# Fastino_References.net
KiCad netlist of a schematic drawn in Altium Designer
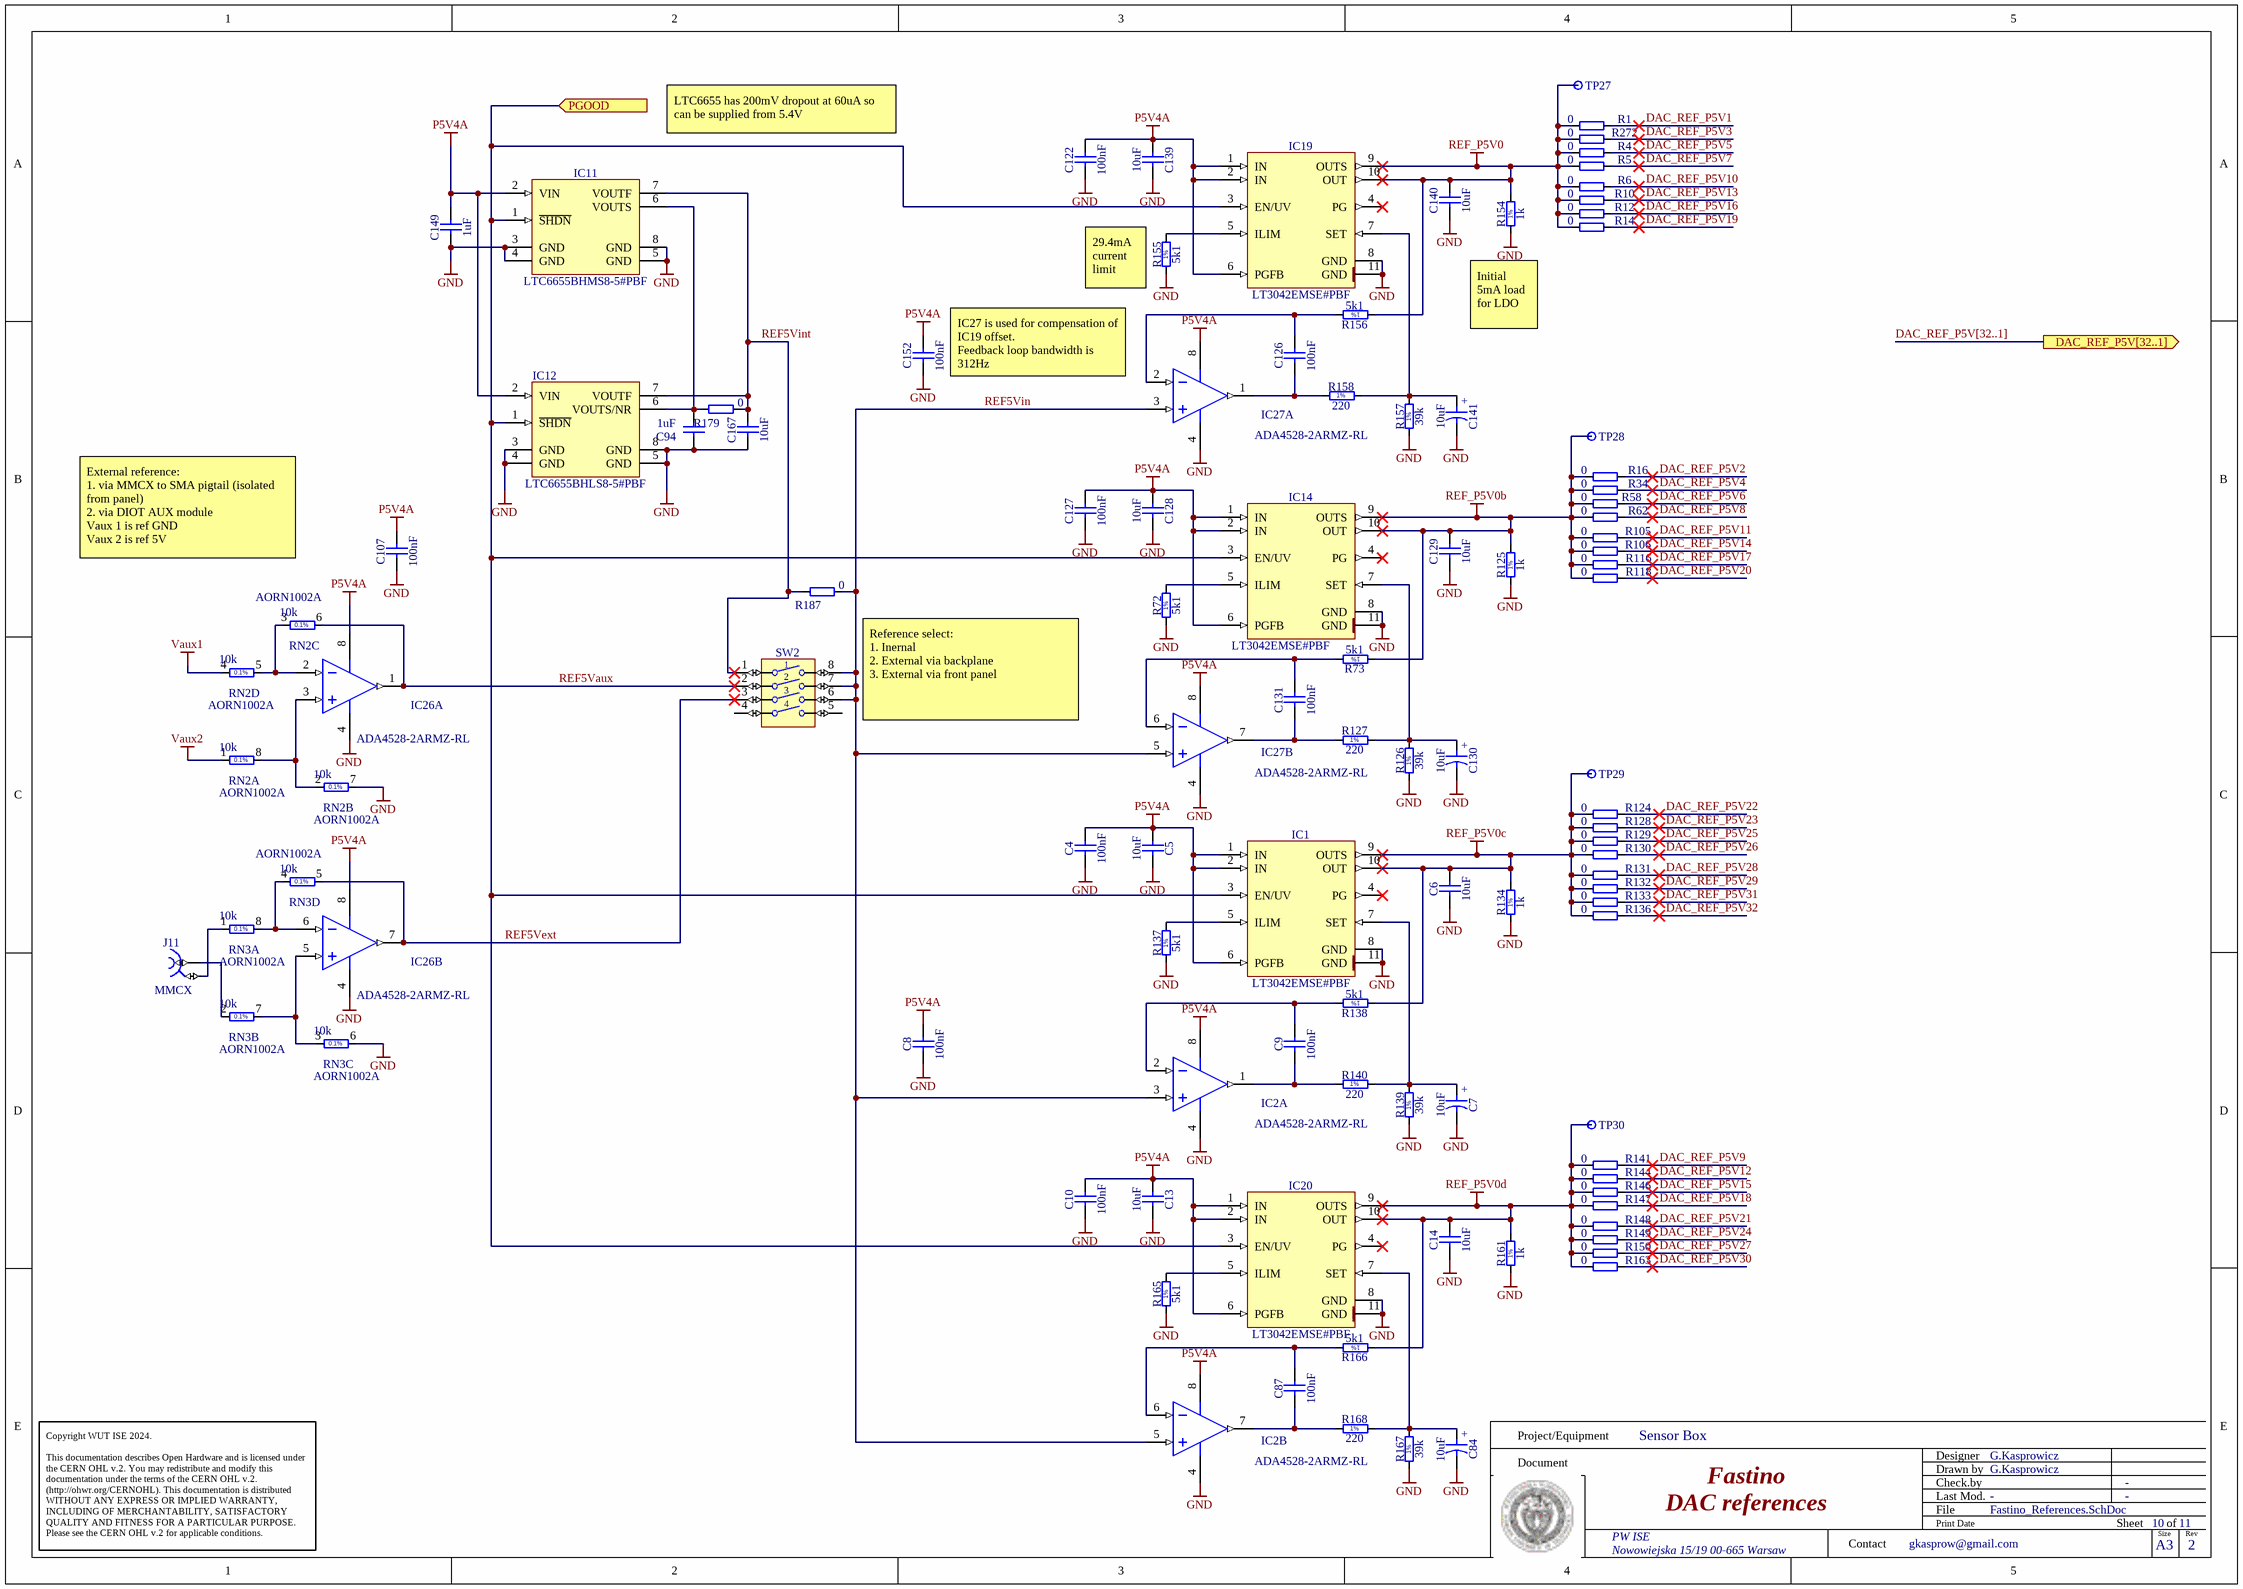
[diagram p0: Fastino_References.SchDoc]

(export (version "E")
  (design (tool "Eeschema 10.0.6"))
  (components
    (comp (ref "C4")
      (value "100nF")
      (footprint "CAPC1005X55N")
      (description "Non-polarised capacitor")
      (fields (field (name "PART NUMBER") "CC0402_100NF_16V_10%_X5R") (field (name "VOLTAGE") "16V"))
      (libsource (lib "Capacitors") (part "Capacitor - non polarized"))
    )
    (comp (ref "C5")
      (value "10uF")
      (footprint "CAPC1608X80N")
      (description "Non-polarised capacitor")
      (fields (field (name "PART NUMBER") "CC0603_10UF_10V_10%_X5R") (field (name "VOLTAGE") "10V"))
      (libsource (lib "Capacitors") (part "Capacitor - non polarized"))
    )
    (comp (ref "C6")
      (value "10uF")
      (footprint "CAPC1608X80N")
      (description "Non-polarised capacitor")
      (fields (field (name "PART NUMBER") "CC0603_10UF_10V_10%_X5R") (field (name "VOLTAGE") "10V"))
      (libsource (lib "Capacitors") (part "Capacitor - non polarized"))
    )
    (comp (ref "C7")
      (value "10uF")
      (footprint "CAPMP3216X180N")
      (description "Polarised capacitor")
      (fields (field (name "PART NUMBER") "CTE3216-18_10UF_16V_20%_AVX_TCJ") (field (name "VOLTAGE") "16V"))
      (libsource (lib "Capacitors") (part "Capacitor - polarized"))
    )
    (comp (ref "C8")
      (value "100nF")
      (footprint "CAPC1005X55N")
      (description "Non-polarised capacitor")
      (fields (field (name "PART NUMBER") "CC0402_100NF_16V_10%_X5R") (field (name "VOLTAGE") "16V"))
      (libsource (lib "Capacitors") (part "Capacitor - non polarized"))
    )
    (comp (ref "C9")
      (value "100nF")
      (footprint "CAPC1005X55N")
      (description "Non-polarised capacitor")
      (fields (field (name "PART NUMBER") "CC0402_100NF_16V_10%_X5R") (field (name "VOLTAGE") "16V"))
      (libsource (lib "Capacitors") (part "Capacitor - non polarized"))
    )
    (comp (ref "C10")
      (value "100nF")
      (footprint "CAPC1005X55N")
      (description "Non-polarised capacitor")
      (fields (field (name "PART NUMBER") "CC0402_100NF_16V_10%_X5R") (field (name "VOLTAGE") "16V"))
      (libsource (lib "Capacitors") (part "Capacitor - non polarized"))
    )
    (comp (ref "C13")
      (value "10uF")
      (footprint "CAPC1608X80N")
      (description "Non-polarised capacitor")
      (fields (field (name "PART NUMBER") "CC0603_10UF_10V_10%_X5R") (field (name "VOLTAGE") "10V"))
      (libsource (lib "Capacitors") (part "Capacitor - non polarized"))
    )
    (comp (ref "C14")
      (value "10uF")
      (footprint "CAPC1608X80N")
      (description "Non-polarised capacitor")
      (fields (field (name "PART NUMBER") "CC0603_10UF_10V_10%_X5R") (field (name "VOLTAGE") "10V"))
      (libsource (lib "Capacitors") (part "Capacitor - non polarized"))
    )
    (comp (ref "C84")
      (value "10uF")
      (footprint "CAPMP3216X180N")
      (description "Polarised capacitor")
      (fields (field (name "PART NUMBER") "CTE3216-18_10UF_16V_20%_AVX_TCJ") (field (name "VOLTAGE") "16V"))
      (libsource (lib "Capacitors") (part "Capacitor - polarized"))
    )
    (comp (ref "C87")
      (value "100nF")
      (footprint "CAPC1005X55N")
      (description "Non-polarised capacitor")
      (fields (field (name "PART NUMBER") "CC0402_100NF_16V_10%_X5R") (field (name "VOLTAGE") "16V"))
      (libsource (lib "Capacitors") (part "Capacitor - non polarized"))
    )
    (comp (ref "C94")
      (value "1uF")
      (footprint "CAPC1608X87N")
      (description "Non-polarised capacitor")
      (fields (field (name "PART NUMBER") "CC0603_1UF_25V_10%_X7R") (field (name "VOLTAGE") "25V"))
      (libsource (lib "Capacitors") (part "Capacitor - non polarized"))
    )
    (comp (ref "C107")
      (value "100nF")
      (footprint "CAPC1005X55N")
      (description "Non-polarised capacitor")
      (fields (field (name "PART NUMBER") "CC0402_100NF_16V_10%_X5R") (field (name "VOLTAGE") "16V"))
      (libsource (lib "Capacitors") (part "Capacitor - non polarized"))
    )
    (comp (ref "C122")
      (value "100nF")
      (footprint "CAPC1005X55N")
      (description "Non-polarised capacitor")
      (fields (field (name "PART NUMBER") "CC0402_100NF_16V_10%_X5R") (field (name "VOLTAGE") "16V"))
      (libsource (lib "Capacitors") (part "Capacitor - non polarized"))
    )
    (comp (ref "C126")
      (value "100nF")
      (footprint "CAPC1005X55N")
      (description "Non-polarised capacitor")
      (fields (field (name "PART NUMBER") "CC0402_100NF_16V_10%_X5R") (field (name "VOLTAGE") "16V"))
      (libsource (lib "Capacitors") (part "Capacitor - non polarized"))
    )
    (comp (ref "C127")
      (value "100nF")
      (footprint "CAPC1005X55N")
      (description "Non-polarised capacitor")
      (fields (field (name "PART NUMBER") "CC0402_100NF_16V_10%_X5R") (field (name "VOLTAGE") "16V"))
      (libsource (lib "Capacitors") (part "Capacitor - non polarized"))
    )
    (comp (ref "C128")
      (value "10uF")
      (footprint "CAPC1608X80N")
      (description "Non-polarised capacitor")
      (fields (field (name "PART NUMBER") "CC0603_10UF_10V_10%_X5R") (field (name "VOLTAGE") "10V"))
      (libsource (lib "Capacitors") (part "Capacitor - non polarized"))
    )
    (comp (ref "C129")
      (value "10uF")
      (footprint "CAPC1608X80N")
      (description "Non-polarised capacitor")
      (fields (field (name "PART NUMBER") "CC0603_10UF_10V_10%_X5R") (field (name "VOLTAGE") "10V"))
      (libsource (lib "Capacitors") (part "Capacitor - non polarized"))
    )
    (comp (ref "C130")
      (value "10uF")
      (footprint "CAPMP3216X180N")
      (description "Polarised capacitor")
      (fields (field (name "PART NUMBER") "CTE3216-18_10UF_16V_20%_AVX_TCJ") (field (name "VOLTAGE") "16V"))
      (libsource (lib "Capacitors") (part "Capacitor - polarized"))
    )
    (comp (ref "C131")
      (value "100nF")
      (footprint "CAPC1005X55N")
      (description "Non-polarised capacitor")
      (fields (field (name "PART NUMBER") "CC0402_100NF_16V_10%_X5R") (field (name "VOLTAGE") "16V"))
      (libsource (lib "Capacitors") (part "Capacitor - non polarized"))
    )
    (comp (ref "C139")
      (value "10uF")
      (footprint "CAPC1608X80N")
      (description "Non-polarised capacitor")
      (fields (field (name "PART NUMBER") "CC0603_10UF_10V_10%_X5R") (field (name "VOLTAGE") "10V"))
      (libsource (lib "Capacitors") (part "Capacitor - non polarized"))
    )
    (comp (ref "C140")
      (value "10uF")
      (footprint "CAPC1608X80N")
      (description "Non-polarised capacitor")
      (fields (field (name "PART NUMBER") "CC0603_10UF_10V_10%_X5R") (field (name "VOLTAGE") "10V"))
      (libsource (lib "Capacitors") (part "Capacitor - non polarized"))
    )
    (comp (ref "C141")
      (value "10uF")
      (footprint "CAPMP3216X180N")
      (description "Polarised capacitor")
      (fields (field (name "PART NUMBER") "CTE3216-18_10UF_16V_20%_AVX_TCJ") (field (name "VOLTAGE") "16V"))
      (libsource (lib "Capacitors") (part "Capacitor - polarized"))
    )
    (comp (ref "C149")
      (value "1uF")
      (footprint "CAPC1608X87N")
      (description "Non-polarised capacitor")
      (fields (field (name "PART NUMBER") "CC0603_1UF_25V_10%_X7R") (field (name "VOLTAGE") "25V"))
      (libsource (lib "Capacitors") (part "Capacitor - non polarized"))
    )
    (comp (ref "C152")
      (value "100nF")
      (footprint "CAPC1005X55N")
      (description "Non-polarised capacitor")
      (fields (field (name "PART NUMBER") "CC0402_100NF_16V_10%_X5R") (field (name "VOLTAGE") "16V"))
      (libsource (lib "Capacitors") (part "Capacitor - non polarized"))
    )
    (comp (ref "C167")
      (value "10uF")
      (footprint "CAPC1608X80N")
      (description "Non-polarised capacitor")
      (fields (field (name "PART NUMBER") "CC0603_10UF_10V_10%_X5R") (field (name "VOLTAGE") "10V"))
      (libsource (lib "Capacitors") (part "Capacitor - non polarized"))
    )
    (comp (ref "IC1")
      (value "LT3042EMSE#PBF")
      (footprint "SOP50P490X110-11N-R168X198")
      (description "20V, 200mA, Ultralow Noise, Ultrahigh PSRR RF Linear Regulator")
      (fields (field (name "MANUFACTURER") "LINEAR TECHNOLOGY"))
      (libsource (lib "ICs And Semiconductors") (part "LT3042"))
    )
    (comp (ref "IC2")
      (value "ADA4528-2ARMZ-RL")
      (footprint "ADI-RM-8_N")
      (fields (field (name "GENERIC PART NUMBER") "ADA4528-2") (field (name "MANUFACTURER") "Analog Devices"))
      (libsource (lib "Altium Content Vault") (part "ADI-ADA4000-2-X-8"))
    )
    (comp (ref "IC11")
      (value "LTC6655BHMS8-5#PBF")
      (footprint "SOP65P490X110-8N")
      (description "0.25ppm Noise, Low Drift Precision Buffered Voltage Reference")
      (fields (field (name "MANUFACTURER") "LINEAR TECHNOLOGY"))
      (libsource (lib "ICs And Semiconductors") (part "LTC6655"))
    )
    (comp (ref "IC12")
      (value "LTC6655BHLS8-5#PBF")
      (footprint "8-CLCC")
      (description "5.0V, 1uA Precision Voltage Reference")
      (fields (field (name "MANUFACTURER") "LINEAR TECHNOLOGY"))
      (libsource (lib "Sampler") (part "REF_LTC6655CHLS8-4.096"))
    )
    (comp (ref "IC14")
      (value "LT3042EMSE#PBF")
      (footprint "SOP50P490X110-11N-R168X198")
      (description "20V, 200mA, Ultralow Noise, Ultrahigh PSRR RF Linear Regulator")
      (fields (field (name "MANUFACTURER") "LINEAR TECHNOLOGY"))
      (libsource (lib "ICs And Semiconductors") (part "LT3042"))
    )
    (comp (ref "IC19")
      (value "LT3042EMSE#PBF")
      (footprint "SOP50P490X110-11N-R168X198")
      (description "20V, 200mA, Ultralow Noise, Ultrahigh PSRR RF Linear Regulator")
      (fields (field (name "MANUFACTURER") "LINEAR TECHNOLOGY"))
      (libsource (lib "ICs And Semiconductors") (part "LT3042"))
    )
    (comp (ref "IC20")
      (value "LT3042EMSE#PBF")
      (footprint "SOP50P490X110-11N-R168X198")
      (description "20V, 200mA, Ultralow Noise, Ultrahigh PSRR RF Linear Regulator")
      (fields (field (name "MANUFACTURER") "LINEAR TECHNOLOGY"))
      (libsource (lib "ICs And Semiconductors") (part "LT3042"))
    )
    (comp (ref "IC26")
      (value "ADA4528-2ARMZ-RL")
      (footprint "ADI-RM-8_N")
      (fields (field (name "GENERIC PART NUMBER") "ADA4528-2") (field (name "MANUFACTURER") "Analog Devices"))
      (libsource (lib "Altium Content Vault") (part "ADI-ADA4000-2-X-8"))
    )
    (comp (ref "IC27")
      (value "ADA4528-2ARMZ-RL")
      (footprint "ADI-RM-8_N")
      (fields (field (name "GENERIC PART NUMBER") "ADA4528-2") (field (name "MANUFACTURER") "Analog Devices"))
      (libsource (lib "Altium Content Vault") (part "ADI-ADA4000-2-X-8"))
    )
    (comp (ref "J11")
      (value "MMCX")
      (footprint "SAMTEC_MMCX-J-P-H-ST-TH1")
      (fields
        (field (name "PART NUMBER") "SAMTEC_MMCX-J-P-H-ST-TH1")
        (field (name "MANUFACTURER") "SAMTEC")
        (field (name "MANUFACTURER PART NUMBER") "MMCX-J-P-H-ST-TH1")
      )
      (libsource (lib "Connectors") (part "Coax_1Female_1Shield"))
    )
    (comp (ref "R1")
      (value "0")
      (footprint "RESC1005X40N")
      (description "Resistor")
      (fields (field (name "PART NUMBER") "R0402_0R_JUMPER") (field (name "MANUFACTURER") "GENERIC"))
      (libsource (lib "Resistors") (part "Resistor"))
    )
    (comp (ref "R4")
      (value "0")
      (footprint "RESC1005X40N")
      (description "Resistor")
      (fields (field (name "PART NUMBER") "R0402_0R_JUMPER") (field (name "MANUFACTURER") "GENERIC"))
      (libsource (lib "Resistors") (part "Resistor"))
    )
    (comp (ref "R5")
      (value "0")
      (footprint "RESC1005X40N")
      (description "Resistor")
      (fields (field (name "PART NUMBER") "R0402_0R_JUMPER") (field (name "MANUFACTURER") "GENERIC"))
      (libsource (lib "Resistors") (part "Resistor"))
    )
    (comp (ref "R6")
      (value "0")
      (footprint "RESC1005X40N")
      (description "Resistor")
      (fields (field (name "PART NUMBER") "R0402_0R_JUMPER") (field (name "MANUFACTURER") "GENERIC"))
      (libsource (lib "Resistors") (part "Resistor"))
    )
    (comp (ref "R10")
      (value "0")
      (footprint "RESC1005X40N")
      (description "Resistor")
      (fields (field (name "PART NUMBER") "R0402_0R_JUMPER") (field (name "MANUFACTURER") "GENERIC"))
      (libsource (lib "Resistors") (part "Resistor"))
    )
    (comp (ref "R12")
      (value "0")
      (footprint "RESC1005X40N")
      (description "Resistor")
      (fields (field (name "PART NUMBER") "R0402_0R_JUMPER") (field (name "MANUFACTURER") "GENERIC"))
      (libsource (lib "Resistors") (part "Resistor"))
    )
    (comp (ref "R14")
      (value "0")
      (footprint "RESC1005X40N")
      (description "Resistor")
      (fields (field (name "PART NUMBER") "R0402_0R_JUMPER") (field (name "MANUFACTURER") "GENERIC"))
      (libsource (lib "Resistors") (part "Resistor"))
    )
    (comp (ref "R16")
      (value "0")
      (footprint "RESC1005X40N")
      (description "Resistor")
      (fields (field (name "PART NUMBER") "R0402_0R_JUMPER") (field (name "MANUFACTURER") "GENERIC"))
      (libsource (lib "Resistors") (part "Resistor"))
    )
    (comp (ref "R34")
      (value "0")
      (footprint "RESC1005X40N")
      (description "Resistor")
      (fields (field (name "PART NUMBER") "R0402_0R_JUMPER") (field (name "MANUFACTURER") "GENERIC"))
      (libsource (lib "Resistors") (part "Resistor"))
    )
    (comp (ref "R58")
      (value "0")
      (footprint "RESC1005X40N")
      (description "Resistor")
      (fields (field (name "PART NUMBER") "R0402_0R_JUMPER") (field (name "MANUFACTURER") "GENERIC"))
      (libsource (lib "Resistors") (part "Resistor"))
    )
    (comp (ref "R62")
      (value "0")
      (footprint "RESC1005X40N")
      (description "Resistor")
      (fields (field (name "PART NUMBER") "R0402_0R_JUMPER") (field (name "MANUFACTURER") "GENERIC"))
      (libsource (lib "Resistors") (part "Resistor"))
    )
    (comp (ref "R72")
      (value "5k1")
      (footprint "RESC1005X40N")
      (description "Resistor - 1%")
      (fields (field (name "PART NUMBER") "R0402_5K1_1%_0.0625W_100PPM") (field (name "POWER") "0.0625W"))
      (libsource (lib "Resistors") (part "Resistor - 1%"))
    )
    (comp (ref "R73")
      (value "5k1")
      (footprint "RESC1005X40N")
      (description "Resistor - 1%")
      (fields (field (name "PART NUMBER") "R0402_5K1_1%_0.0625W_100PPM") (field (name "POWER") "0.0625W"))
      (libsource (lib "Resistors") (part "Resistor - 1%"))
    )
    (comp (ref "R105")
      (value "0")
      (footprint "RESC1005X40N")
      (description "Resistor")
      (fields (field (name "PART NUMBER") "R0402_0R_JUMPER") (field (name "MANUFACTURER") "GENERIC"))
      (libsource (lib "Resistors") (part "Resistor"))
    )
    (comp (ref "R106")
      (value "0")
      (footprint "RESC1005X40N")
      (description "Resistor")
      (fields (field (name "PART NUMBER") "R0402_0R_JUMPER") (field (name "MANUFACTURER") "GENERIC"))
      (libsource (lib "Resistors") (part "Resistor"))
    )
    (comp (ref "R116")
      (value "0")
      (footprint "RESC1005X40N")
      (description "Resistor")
      (fields (field (name "PART NUMBER") "R0402_0R_JUMPER") (field (name "MANUFACTURER") "GENERIC"))
      (libsource (lib "Resistors") (part "Resistor"))
    )
    (comp (ref "R118")
      (value "0")
      (footprint "RESC1005X40N")
      (description "Resistor")
      (fields (field (name "PART NUMBER") "R0402_0R_JUMPER") (field (name "MANUFACTURER") "GENERIC"))
      (libsource (lib "Resistors") (part "Resistor"))
    )
    (comp (ref "R124")
      (value "0")
      (footprint "RESC1005X40N")
      (description "Resistor")
      (fields (field (name "PART NUMBER") "R0402_0R_JUMPER") (field (name "MANUFACTURER") "GENERIC"))
      (libsource (lib "Resistors") (part "Resistor"))
    )
    (comp (ref "R125")
      (value "1k")
      (footprint "RESC1005X40N")
      (description "Resistor - 1%")
      (fields (field (name "PART NUMBER") "R0402_1K_1%_0.0625W_100PPM") (field (name "POWER") "0.0625W"))
      (libsource (lib "Resistors") (part "Resistor - 1%"))
    )
    (comp (ref "R126")
      (value "39k")
      (footprint "RESC1608X55N")
      (description "Resistor - 1%")
      (fields (field (name "PART NUMBER") "R0603_39K_1%_0.1W_100PPM") (field (name "POWER") "0.1W"))
      (libsource (lib "Resistors") (part "Resistor - 1%"))
    )
    (comp (ref "R127")
      (value "220")
      (footprint "RESC1005X40N")
      (description "Resistor - 1%")
      (fields (field (name "PART NUMBER") "R0402_220R_1%_0.0625W_100PPM") (field (name "POWER") "0.0625W"))
      (libsource (lib "Resistors") (part "Resistor - 1%"))
    )
    (comp (ref "R128")
      (value "0")
      (footprint "RESC1005X40N")
      (description "Resistor")
      (fields (field (name "PART NUMBER") "R0402_0R_JUMPER") (field (name "MANUFACTURER") "GENERIC"))
      (libsource (lib "Resistors") (part "Resistor"))
    )
    (comp (ref "R129")
      (value "0")
      (footprint "RESC1005X40N")
      (description "Resistor")
      (fields (field (name "PART NUMBER") "R0402_0R_JUMPER") (field (name "MANUFACTURER") "GENERIC"))
      (libsource (lib "Resistors") (part "Resistor"))
    )
    (comp (ref "R130")
      (value "0")
      (footprint "RESC1005X40N")
      (description "Resistor")
      (fields (field (name "PART NUMBER") "R0402_0R_JUMPER") (field (name "MANUFACTURER") "GENERIC"))
      (libsource (lib "Resistors") (part "Resistor"))
    )
    (comp (ref "R131")
      (value "0")
      (footprint "RESC1005X40N")
      (description "Resistor")
      (fields (field (name "PART NUMBER") "R0402_0R_JUMPER") (field (name "MANUFACTURER") "GENERIC"))
      (libsource (lib "Resistors") (part "Resistor"))
    )
    (comp (ref "R132")
      (value "0")
      (footprint "RESC1005X40N")
      (description "Resistor")
      (fields (field (name "PART NUMBER") "R0402_0R_JUMPER") (field (name "MANUFACTURER") "GENERIC"))
      (libsource (lib "Resistors") (part "Resistor"))
    )
    (comp (ref "R133")
      (value "0")
      (footprint "RESC1005X40N")
      (description "Resistor")
      (fields (field (name "PART NUMBER") "R0402_0R_JUMPER") (field (name "MANUFACTURER") "GENERIC"))
      (libsource (lib "Resistors") (part "Resistor"))
    )
    (comp (ref "R134")
      (value "1k")
      (footprint "RESC1005X40N")
      (description "Resistor - 1%")
      (fields (field (name "PART NUMBER") "R0402_1K_1%_0.0625W_100PPM") (field (name "POWER") "0.0625W"))
      (libsource (lib "Resistors") (part "Resistor - 1%"))
    )
    (comp (ref "R136")
      (value "0")
      (footprint "RESC1005X40N")
      (description "Resistor")
      (fields (field (name "PART NUMBER") "R0402_0R_JUMPER") (field (name "MANUFACTURER") "GENERIC"))
      (libsource (lib "Resistors") (part "Resistor"))
    )
    (comp (ref "R137")
      (value "5k1")
      (footprint "RESC1005X40N")
      (description "Resistor - 1%")
      (fields (field (name "PART NUMBER") "R0402_5K1_1%_0.0625W_100PPM") (field (name "POWER") "0.0625W"))
      (libsource (lib "Resistors") (part "Resistor - 1%"))
    )
    (comp (ref "R138")
      (value "5k1")
      (footprint "RESC1005X40N")
      (description "Resistor - 1%")
      (fields (field (name "PART NUMBER") "R0402_5K1_1%_0.0625W_100PPM") (field (name "POWER") "0.0625W"))
      (libsource (lib "Resistors") (part "Resistor - 1%"))
    )
    (comp (ref "R139")
      (value "39k")
      (footprint "RESC1608X55N")
      (description "Resistor - 1%")
      (fields (field (name "PART NUMBER") "R0603_39K_1%_0.1W_100PPM") (field (name "POWER") "0.1W"))
      (libsource (lib "Resistors") (part "Resistor - 1%"))
    )
    (comp (ref "R140")
      (value "220")
      (footprint "RESC1005X40N")
      (description "Resistor - 1%")
      (fields (field (name "PART NUMBER") "R0402_220R_1%_0.0625W_100PPM") (field (name "POWER") "0.0625W"))
      (libsource (lib "Resistors") (part "Resistor - 1%"))
    )
    (comp (ref "R141")
      (value "0")
      (footprint "RESC1005X40N")
      (description "Resistor")
      (fields (field (name "PART NUMBER") "R0402_0R_JUMPER") (field (name "MANUFACTURER") "GENERIC"))
      (libsource (lib "Resistors") (part "Resistor"))
    )
    (comp (ref "R144")
      (value "0")
      (footprint "RESC1005X40N")
      (description "Resistor")
      (fields (field (name "PART NUMBER") "R0402_0R_JUMPER") (field (name "MANUFACTURER") "GENERIC"))
      (libsource (lib "Resistors") (part "Resistor"))
    )
    (comp (ref "R146")
      (value "0")
      (footprint "RESC1005X40N")
      (description "Resistor")
      (fields (field (name "PART NUMBER") "R0402_0R_JUMPER") (field (name "MANUFACTURER") "GENERIC"))
      (libsource (lib "Resistors") (part "Resistor"))
    )
    (comp (ref "R147")
      (value "0")
      (footprint "RESC1005X40N")
      (description "Resistor")
      (fields (field (name "PART NUMBER") "R0402_0R_JUMPER") (field (name "MANUFACTURER") "GENERIC"))
      (libsource (lib "Resistors") (part "Resistor"))
    )
    (comp (ref "R148")
      (value "0")
      (footprint "RESC1005X40N")
      (description "Resistor")
      (fields (field (name "PART NUMBER") "R0402_0R_JUMPER") (field (name "MANUFACTURER") "GENERIC"))
      (libsource (lib "Resistors") (part "Resistor"))
    )
    (comp (ref "R149")
      (value "0")
      (footprint "RESC1005X40N")
      (description "Resistor")
      (fields (field (name "PART NUMBER") "R0402_0R_JUMPER") (field (name "MANUFACTURER") "GENERIC"))
      (libsource (lib "Resistors") (part "Resistor"))
    )
    (comp (ref "R150")
      (value "0")
      (footprint "RESC1005X40N")
      (description "Resistor")
      (fields (field (name "PART NUMBER") "R0402_0R_JUMPER") (field (name "MANUFACTURER") "GENERIC"))
      (libsource (lib "Resistors") (part "Resistor"))
    )
    (comp (ref "R154")
      (value "1k")
      (footprint "RESC1005X40N")
      (description "Resistor - 1%")
      (fields (field (name "PART NUMBER") "R0402_1K_1%_0.0625W_100PPM") (field (name "POWER") "0.0625W"))
      (libsource (lib "Resistors") (part "Resistor - 1%"))
    )
    (comp (ref "R155")
      (value "5k1")
      (footprint "RESC1005X40N")
      (description "Resistor - 1%")
      (fields (field (name "PART NUMBER") "R0402_5K1_1%_0.0625W_100PPM") (field (name "POWER") "0.0625W"))
      (libsource (lib "Resistors") (part "Resistor - 1%"))
    )
    (comp (ref "R156")
      (value "5k1")
      (footprint "RESC1005X40N")
      (description "Resistor - 1%")
      (fields (field (name "PART NUMBER") "R0402_5K1_1%_0.0625W_100PPM") (field (name "POWER") "0.0625W"))
      (libsource (lib "Resistors") (part "Resistor - 1%"))
    )
    (comp (ref "R157")
      (value "39k")
      (footprint "RESC1608X55N")
      (description "Resistor - 1%")
      (fields (field (name "PART NUMBER") "R0603_39K_1%_0.1W_100PPM") (field (name "POWER") "0.1W"))
      (libsource (lib "Resistors") (part "Resistor - 1%"))
    )
    (comp (ref "R158")
      (value "220")
      (footprint "RESC1005X40N")
      (description "Resistor - 1%")
      (fields (field (name "PART NUMBER") "R0402_220R_1%_0.0625W_100PPM") (field (name "POWER") "0.0625W"))
      (libsource (lib "Resistors") (part "Resistor - 1%"))
    )
    (comp (ref "R161")
      (value "1k")
      (footprint "RESC1005X40N")
      (description "Resistor - 1%")
      (fields (field (name "PART NUMBER") "R0402_1K_1%_0.0625W_100PPM") (field (name "POWER") "0.0625W"))
      (libsource (lib "Resistors") (part "Resistor - 1%"))
    )
    (comp (ref "R163")
      (value "0")
      (footprint "RESC1005X40N")
      (description "Resistor")
      (fields (field (name "PART NUMBER") "R0402_0R_JUMPER") (field (name "MANUFACTURER") "GENERIC"))
      (libsource (lib "Resistors") (part "Resistor"))
    )
    (comp (ref "R165")
      (value "5k1")
      (footprint "RESC1005X40N")
      (description "Resistor - 1%")
      (fields (field (name "PART NUMBER") "R0402_5K1_1%_0.0625W_100PPM") (field (name "POWER") "0.0625W"))
      (libsource (lib "Resistors") (part "Resistor - 1%"))
    )
    (comp (ref "R166")
      (value "5k1")
      (footprint "RESC1005X40N")
      (description "Resistor - 1%")
      (fields (field (name "PART NUMBER") "R0402_5K1_1%_0.0625W_100PPM") (field (name "POWER") "0.0625W"))
      (libsource (lib "Resistors") (part "Resistor - 1%"))
    )
    (comp (ref "R167")
      (value "39k")
      (footprint "RESC1608X55N")
      (description "Resistor - 1%")
      (fields (field (name "PART NUMBER") "R0603_39K_1%_0.1W_100PPM") (field (name "POWER") "0.1W"))
      (libsource (lib "Resistors") (part "Resistor - 1%"))
    )
    (comp (ref "R168")
      (value "220")
      (footprint "RESC1005X40N")
      (description "Resistor - 1%")
      (fields (field (name "PART NUMBER") "R0402_220R_1%_0.0625W_100PPM") (field (name "POWER") "0.0625W"))
      (libsource (lib "Resistors") (part "Resistor - 1%"))
    )
    (comp (ref "R179")
      (value "0")
      (footprint "RESC1005X40N")
      (description "Resistor")
      (fields (field (name "PART NUMBER") "R0402_0R_JUMPER") (field (name "MANUFACTURER") "GENERIC"))
      (libsource (lib "Resistors") (part "Resistor"))
    )
    (comp (ref "R187")
      (value "0")
      (footprint "RESC1005X40N")
      (description "Resistor")
      (fields (field (name "PART NUMBER") "R0402_0R_JUMPER") (field (name "MANUFACTURER") "GENERIC"))
      (libsource (lib "Resistors") (part "Resistor"))
    )
    (comp (ref "R272")
      (value "0")
      (footprint "RESC1005X40N")
      (description "Resistor")
      (fields (field (name "PART NUMBER") "R0402_0R_JUMPER") (field (name "MANUFACTURER") "GENERIC"))
      (libsource (lib "Resistors") (part "Resistor"))
    )
    (comp (ref "RN2")
      (value "10k")
      (footprint "SOIC127P600X175-8N")
      (description "DIL8 Resistor Network 4 Isolated Resistor 0.1%")
      (fields
        (field (name "PART NUMBER") "RN_10K_VISHAY_AORN1002A")
        (field (name "POWER") "4x0.1W")
        (field (name "MANUFACTURER PART NUMBER") "AORN1002A")
      )
      (libsource (lib "Resistors") (part "RN DIL8_4xR_Isolated_0.1%"))
    )
    (comp (ref "RN3")
      (value "10k")
      (footprint "SOIC127P600X175-8N")
      (description "DIL8 Resistor Network 4 Isolated Resistor 0.1%")
      (fields
        (field (name "PART NUMBER") "RN_10K_VISHAY_AORN1002A")
        (field (name "POWER") "4x0.1W")
        (field (name "MANUFACTURER PART NUMBER") "AORN1002A")
      )
      (libsource (lib "Resistors") (part "RN DIL8_4xR_Isolated_0.1%"))
    )
    (comp (ref "SW2")
      (value "Switch")
      (footprint "SW_TYCO_1571983-4")
      (description "4 Ways SPST DIP Switch")
      (fields (field (name "PART NUMBER") "SW_TYCO_1571983-4") (field (name "MANUFACTURER") "TYCO"))
      (libsource (lib "Eletro-mechanical") (part "SW 4x SPST DIP Switch"))
    )
    (comp (ref "TP27")
      (value "Test Point")
      (footprint "TPS127")
      (fields (field (name "PART NUMBER") "SMD_PAD_1.27X1.27MM"))
      (libsource (lib "Eletro-mechanical") (part "Test Point"))
    )
    (comp (ref "TP28")
      (value "Test Point")
      (footprint "TPS127")
      (fields (field (name "PART NUMBER") "SMD_PAD_1.27X1.27MM"))
      (libsource (lib "Eletro-mechanical") (part "Test Point"))
    )
    (comp (ref "TP29")
      (value "Test Point")
      (footprint "TPS127")
      (fields (field (name "PART NUMBER") "SMD_PAD_1.27X1.27MM"))
      (libsource (lib "Eletro-mechanical") (part "Test Point"))
    )
    (comp (ref "TP30")
      (value "Test Point")
      (footprint "TPS127")
      (fields (field (name "PART NUMBER") "SMD_PAD_1.27X1.27MM"))
      (libsource (lib "Eletro-mechanical") (part "Test Point"))
    )
  )
  (nets
    (net (code "1") (name "/DAC_REF_P5V1") (class "Default")
      (node (ref "R1") (pin "2") (pinfunction "2_2") (pintype "passive"))
    )
    (net (code "2") (name "/DAC_REF_P5V2") (class "Default")
      (node (ref "R16") (pin "2") (pinfunction "2_2") (pintype "passive"))
    )
    (net (code "3") (name "/DAC_REF_P5V3") (class "Default")
      (node (ref "R272") (pin "2") (pinfunction "2_2") (pintype "passive"))
    )
    (net (code "4") (name "/DAC_REF_P5V4") (class "Default")
      (node (ref "R34") (pin "2") (pinfunction "2_2") (pintype "passive"))
    )
    (net (code "5") (name "/DAC_REF_P5V5") (class "Default")
      (node (ref "R4") (pin "2") (pinfunction "2_2") (pintype "passive"))
    )
    (net (code "6") (name "/DAC_REF_P5V6") (class "Default")
      (node (ref "R58") (pin "2") (pinfunction "2_2") (pintype "passive"))
    )
    (net (code "7") (name "/DAC_REF_P5V7") (class "Default")
      (node (ref "R5") (pin "2") (pinfunction "2_2") (pintype "passive"))
    )
    (net (code "8") (name "/DAC_REF_P5V8") (class "Default")
      (node (ref "R62") (pin "2") (pinfunction "2_2") (pintype "passive"))
    )
    (net (code "9") (name "/DAC_REF_P5V9") (class "Default")
      (node (ref "R141") (pin "2") (pinfunction "2_2") (pintype "passive"))
    )
    (net (code "10") (name "/DAC_REF_P5V10") (class "Default")
      (node (ref "R6") (pin "2") (pinfunction "2_2") (pintype "passive"))
    )
    (net (code "11") (name "/DAC_REF_P5V11") (class "Default")
      (node (ref "R105") (pin "2") (pinfunction "2_2") (pintype "passive"))
    )
    (net (code "12") (name "/DAC_REF_P5V12") (class "Default")
      (node (ref "R144") (pin "2") (pinfunction "2_2") (pintype "passive"))
    )
    (net (code "13") (name "/DAC_REF_P5V13") (class "Default")
      (node (ref "R10") (pin "2") (pinfunction "2_2") (pintype "passive"))
    )
    (net (code "14") (name "/DAC_REF_P5V14") (class "Default")
      (node (ref "R106") (pin "2") (pinfunction "2_2") (pintype "passive"))
    )
    (net (code "15") (name "/DAC_REF_P5V15") (class "Default")
      (node (ref "R146") (pin "2") (pinfunction "2_2") (pintype "passive"))
    )
    (net (code "16") (name "/DAC_REF_P5V16") (class "Default")
      (node (ref "R12") (pin "2") (pinfunction "2_2") (pintype "passive"))
    )
    (net (code "17") (name "/DAC_REF_P5V17") (class "Default")
      (node (ref "R116") (pin "2") (pinfunction "2_2") (pintype "passive"))
    )
    (net (code "18") (name "/DAC_REF_P5V18") (class "Default")
      (node (ref "R147") (pin "2") (pinfunction "2_2") (pintype "passive"))
    )
    (net (code "19") (name "/DAC_REF_P5V19") (class "Default")
      (node (ref "R14") (pin "2") (pinfunction "2_2") (pintype "passive"))
    )
    (net (code "20") (name "/DAC_REF_P5V20") (class "Default")
      (node (ref "R118") (pin "2") (pinfunction "2_2") (pintype "passive"))
    )
    (net (code "21") (name "/DAC_REF_P5V21") (class "Default")
      (node (ref "R148") (pin "2") (pinfunction "2_2") (pintype "passive"))
    )
    (net (code "22") (name "/DAC_REF_P5V22") (class "Default")
      (node (ref "R124") (pin "2") (pinfunction "2_2") (pintype "passive"))
    )
    (net (code "23") (name "/DAC_REF_P5V23") (class "Default")
      (node (ref "R128") (pin "2") (pinfunction "2_2") (pintype "passive"))
    )
    (net (code "24") (name "/DAC_REF_P5V24") (class "Default")
      (node (ref "R149") (pin "2") (pinfunction "2_2") (pintype "passive"))
    )
    (net (code "25") (name "/DAC_REF_P5V25") (class "Default")
      (node (ref "R129") (pin "2") (pinfunction "2_2") (pintype "passive"))
    )
    (net (code "26") (name "/DAC_REF_P5V26") (class "Default")
      (node (ref "R130") (pin "2") (pinfunction "2_2") (pintype "passive"))
    )
    (net (code "27") (name "/DAC_REF_P5V27") (class "Default")
      (node (ref "R150") (pin "2") (pinfunction "2_2") (pintype "passive"))
    )
    (net (code "28") (name "/DAC_REF_P5V28") (class "Default")
      (node (ref "R131") (pin "2") (pinfunction "2_2") (pintype "passive"))
    )
    (net (code "29") (name "/DAC_REF_P5V29") (class "Default")
      (node (ref "R132") (pin "2") (pinfunction "2_2") (pintype "passive"))
    )
    (net (code "30") (name "/DAC_REF_P5V30") (class "Default")
      (node (ref "R163") (pin "2") (pinfunction "2_2") (pintype "passive"))
    )
    (net (code "31") (name "/DAC_REF_P5V31") (class "Default")
      (node (ref "R133") (pin "2") (pinfunction "2_2") (pintype "passive"))
    )
    (net (code "32") (name "/DAC_REF_P5V32") (class "Default")
      (node (ref "R136") (pin "2") (pinfunction "2_2") (pintype "passive"))
    )
    (net (code "34") (name "/PGOOD") (class "Default")
      (node (ref "IC1") (pin "3") (pinfunction "EN/UV_3") (pintype "input"))
      (node (ref "IC11") (pin "1") (pinfunction "~{SHDN}_1") (pintype "input"))
      (node (ref "IC12") (pin "1") (pinfunction "~{SHDN}_1") (pintype "input"))
      (node (ref "IC14") (pin "3") (pinfunction "EN/UV_3") (pintype "input"))
      (node (ref "IC19") (pin "3") (pinfunction "EN/UV_3") (pintype "input"))
      (node (ref "IC20") (pin "3") (pinfunction "EN/UV_3") (pintype "input"))
    )
    (net (code "35") (name "/REF5Vaux") (class "Default")
      (node (ref "IC26") (pin "1") (pinfunction "OUT_A_1") (pintype "output"))
      (node (ref "RN2") (pin "6") (pinfunction "6_6") (pintype "passive"))
      (node (ref "SW2") (pin "2") (pinfunction "2_2") (pintype "bidirectional"))
    )
    (net (code "36") (name "/REF5Vext") (class "Default")
      (node (ref "IC26") (pin "7") (pinfunction "OUT_B_7") (pintype "output"))
      (node (ref "RN3") (pin "5") (pinfunction "5_5") (pintype "passive"))
      (node (ref "SW2") (pin "3") (pinfunction "3_3") (pintype "bidirectional"))
    )
    (net (code "37") (name "/REF5Vin") (class "Default")
      (node (ref "IC2") (pin "3") (pinfunction "+IN_A_3") (pintype "input"))
      (node (ref "IC2") (pin "5") (pinfunction "+IN_B_5") (pintype "input"))
      (node (ref "IC27") (pin "3") (pinfunction "+IN_A_3") (pintype "input"))
      (node (ref "IC27") (pin "5") (pinfunction "+IN_B_5") (pintype "input"))
      (node (ref "R187") (pin "2") (pinfunction "2_2") (pintype "passive"))
      (node (ref "SW2") (pin "6") (pinfunction "6_6") (pintype "bidirectional"))
      (node (ref "SW2") (pin "7") (pinfunction "7_7") (pintype "bidirectional"))
      (node (ref "SW2") (pin "8") (pinfunction "8_8") (pintype "bidirectional"))
    )
    (net (code "38") (name "/REF5Vint") (class "Default")
      (node (ref "C167") (pin "2") (pinfunction "2_2") (pintype "passive"))
      (node (ref "IC11") (pin "7") (pinfunction "VOUTF_7") (pintype "power_in"))
      (node (ref "IC12") (pin "7") (pinfunction "VOUTF_7") (pintype "power_in"))
      (node (ref "R179") (pin "2") (pinfunction "2_2") (pintype "passive"))
      (node (ref "R187") (pin "1") (pinfunction "1_1") (pintype "passive"))
      (node (ref "SW2") (pin "1") (pinfunction "1_1") (pintype "bidirectional"))
    )
    (net (code "39") (name "GND") (class "Default")
      (node (ref "C10") (pin "1") (pinfunction "1_1") (pintype "passive"))
      (node (ref "C107") (pin "1") (pinfunction "1_1") (pintype "passive"))
      (node (ref "C122") (pin "1") (pinfunction "1_1") (pintype "passive"))
      (node (ref "C127") (pin "1") (pinfunction "1_1") (pintype "passive"))
      (node (ref "C128") (pin "2") (pinfunction "2_2") (pintype "passive"))
      (node (ref "C129") (pin "1") (pinfunction "1_1") (pintype "passive"))
      (node (ref "C13") (pin "2") (pinfunction "2_2") (pintype "passive"))
      (node (ref "C130") (pin "2") (pinfunction "2_2") (pintype "passive"))
      (node (ref "C139") (pin "2") (pinfunction "2_2") (pintype "passive"))
      (node (ref "C14") (pin "1") (pinfunction "1_1") (pintype "passive"))
      (node (ref "C140") (pin "1") (pinfunction "1_1") (pintype "passive"))
      (node (ref "C141") (pin "2") (pinfunction "2_2") (pintype "passive"))
      (node (ref "C149") (pin "1") (pinfunction "1_1") (pintype "passive"))
      (node (ref "C152") (pin "1") (pinfunction "1_1") (pintype "passive"))
      (node (ref "C167") (pin "1") (pinfunction "1_1") (pintype "passive"))
      (node (ref "C4") (pin "1") (pinfunction "1_1") (pintype "passive"))
      (node (ref "C5") (pin "2") (pinfunction "2_2") (pintype "passive"))
      (node (ref "C6") (pin "1") (pinfunction "1_1") (pintype "passive"))
      (node (ref "C7") (pin "2") (pinfunction "2_2") (pintype "passive"))
      (node (ref "C8") (pin "1") (pinfunction "1_1") (pintype "passive"))
      (node (ref "C84") (pin "2") (pinfunction "2_2") (pintype "passive"))
      (node (ref "C94") (pin "1") (pinfunction "1_1") (pintype "passive"))
      (node (ref "IC1") (pin "11") (pinfunction "GND_11") (pintype "power_in"))
      (node (ref "IC1") (pin "8") (pinfunction "GND_8") (pintype "power_in"))
      (node (ref "IC11") (pin "3") (pinfunction "GND_3") (pintype "power_in"))
      (node (ref "IC11") (pin "4") (pinfunction "GND_4") (pintype "power_in"))
      (node (ref "IC11") (pin "5") (pinfunction "GND_5") (pintype "power_in"))
      (node (ref "IC11") (pin "8") (pinfunction "GND_8") (pintype "power_in"))
      (node (ref "IC12") (pin "3") (pinfunction "GND_3") (pintype "power_in"))
      (node (ref "IC12") (pin "4") (pinfunction "GND_4") (pintype "power_in"))
      (node (ref "IC12") (pin "5") (pinfunction "GND_5") (pintype "power_in"))
      (node (ref "IC12") (pin "8") (pinfunction "GND_8") (pintype "power_in"))
      (node (ref "IC14") (pin "11") (pinfunction "GND_11") (pintype "power_in"))
      (node (ref "IC14") (pin "8") (pinfunction "GND_8") (pintype "power_in"))
      (node (ref "IC19") (pin "11") (pinfunction "GND_11") (pintype "power_in"))
      (node (ref "IC19") (pin "8") (pinfunction "GND_8") (pintype "power_in"))
      (node (ref "IC2") (pin "4") (pinfunction "-V_4") (pintype "power_in"))
      (node (ref "IC20") (pin "11") (pinfunction "GND_11") (pintype "power_in"))
      (node (ref "IC20") (pin "8") (pinfunction "GND_8") (pintype "power_in"))
      (node (ref "IC26") (pin "4") (pinfunction "-V_4") (pintype "power_in"))
      (node (ref "IC27") (pin "4") (pinfunction "-V_4") (pintype "power_in"))
      (node (ref "R125") (pin "1") (pinfunction "1_1") (pintype "passive"))
      (node (ref "R126") (pin "1") (pinfunction "1_1") (pintype "passive"))
      (node (ref "R134") (pin "1") (pinfunction "1_1") (pintype "passive"))
      (node (ref "R137") (pin "1") (pinfunction "1_1") (pintype "passive"))
      (node (ref "R139") (pin "1") (pinfunction "1_1") (pintype "passive"))
      (node (ref "R154") (pin "1") (pinfunction "1_1") (pintype "passive"))
      (node (ref "R155") (pin "1") (pinfunction "1_1") (pintype "passive"))
      (node (ref "R157") (pin "1") (pinfunction "1_1") (pintype "passive"))
      (node (ref "R161") (pin "1") (pinfunction "1_1") (pintype "passive"))
      (node (ref "R165") (pin "1") (pinfunction "1_1") (pintype "passive"))
      (node (ref "R167") (pin "1") (pinfunction "1_1") (pintype "passive"))
      (node (ref "R72") (pin "1") (pinfunction "1_1") (pintype "passive"))
      (node (ref "RN2") (pin "7") (pinfunction "7_7") (pintype "passive"))
      (node (ref "RN3") (pin "6") (pinfunction "6_6") (pintype "passive"))
    )
    (net (code "40") (name "Net-(IC1-ILIM)") (class "Default")
      (node (ref "IC1") (pin "5") (pinfunction "ILIM_5") (pintype "input"))
      (node (ref "R137") (pin "2") (pinfunction "2_2") (pintype "passive"))
    )
    (net (code "41") (name "Net-(IC1-SET)") (class "Default")
      (node (ref "C7") (pin "1") (pinfunction "1_1") (pintype "passive"))
      (node (ref "IC1") (pin "7") (pinfunction "SET_7") (pintype "input"))
      (node (ref "R139") (pin "2") (pinfunction "2_2") (pintype "passive"))
      (node (ref "R140") (pin "2") (pinfunction "2_2") (pintype "passive"))
    )
    (net (code "42") (name "Net-(IC2A--IN_A)") (class "Default")
      (node (ref "C9") (pin "2") (pinfunction "2_2") (pintype "passive"))
      (node (ref "IC2") (pin "2") (pinfunction "-IN_A_2") (pintype "input"))
      (node (ref "R138") (pin "2") (pinfunction "2_2") (pintype "passive"))
    )
    (net (code "43") (name "Net-(IC2A-OUT_A)") (class "Default")
      (node (ref "C9") (pin "1") (pinfunction "1_1") (pintype "passive"))
      (node (ref "IC2") (pin "1") (pinfunction "OUT_A_1") (pintype "output"))
      (node (ref "R140") (pin "1") (pinfunction "1_1") (pintype "passive"))
    )
    (net (code "44") (name "Net-(IC2B--IN_B)") (class "Default")
      (node (ref "C87") (pin "2") (pinfunction "2_2") (pintype "passive"))
      (node (ref "IC2") (pin "6") (pinfunction "-IN_B_6") (pintype "input"))
      (node (ref "R166") (pin "2") (pinfunction "2_2") (pintype "passive"))
    )
    (net (code "45") (name "Net-(IC2B-OUT_B)") (class "Default")
      (node (ref "C87") (pin "1") (pinfunction "1_1") (pintype "passive"))
      (node (ref "IC2") (pin "7") (pinfunction "OUT_B_7") (pintype "output"))
      (node (ref "R168") (pin "1") (pinfunction "1_1") (pintype "passive"))
    )
    (net (code "46") (name "Net-(IC11-VOUTS)") (class "Default")
      (node (ref "C94") (pin "2") (pinfunction "2_2") (pintype "passive"))
      (node (ref "IC11") (pin "6") (pinfunction "VOUTS_6") (pintype "power_in"))
      (node (ref "IC12") (pin "6") (pinfunction "VOUTS/NR_6") (pintype "power_in"))
      (node (ref "R179") (pin "1") (pinfunction "1_1") (pintype "passive"))
    )
    (net (code "47") (name "Net-(IC14-ILIM)") (class "Default")
      (node (ref "IC14") (pin "5") (pinfunction "ILIM_5") (pintype "input"))
      (node (ref "R72") (pin "2") (pinfunction "2_2") (pintype "passive"))
    )
    (net (code "48") (name "Net-(IC14-SET)") (class "Default")
      (node (ref "C130") (pin "1") (pinfunction "1_1") (pintype "passive"))
      (node (ref "IC14") (pin "7") (pinfunction "SET_7") (pintype "input"))
      (node (ref "R126") (pin "2") (pinfunction "2_2") (pintype "passive"))
      (node (ref "R127") (pin "2") (pinfunction "2_2") (pintype "passive"))
    )
    (net (code "49") (name "Net-(IC19-ILIM)") (class "Default")
      (node (ref "IC19") (pin "5") (pinfunction "ILIM_5") (pintype "input"))
      (node (ref "R155") (pin "2") (pinfunction "2_2") (pintype "passive"))
    )
    (net (code "50") (name "Net-(IC19-SET)") (class "Default")
      (node (ref "C141") (pin "1") (pinfunction "1_1") (pintype "passive"))
      (node (ref "IC19") (pin "7") (pinfunction "SET_7") (pintype "input"))
      (node (ref "R157") (pin "2") (pinfunction "2_2") (pintype "passive"))
      (node (ref "R158") (pin "2") (pinfunction "2_2") (pintype "passive"))
    )
    (net (code "51") (name "Net-(IC20-ILIM)") (class "Default")
      (node (ref "IC20") (pin "5") (pinfunction "ILIM_5") (pintype "input"))
      (node (ref "R165") (pin "2") (pinfunction "2_2") (pintype "passive"))
    )
    (net (code "52") (name "Net-(IC20-SET)") (class "Default")
      (node (ref "C84") (pin "1") (pinfunction "1_1") (pintype "passive"))
      (node (ref "IC20") (pin "7") (pinfunction "SET_7") (pintype "input"))
      (node (ref "R167") (pin "2") (pinfunction "2_2") (pintype "passive"))
      (node (ref "R168") (pin "2") (pinfunction "2_2") (pintype "passive"))
    )
    (net (code "53") (name "Net-(IC26A-+IN_A)") (class "Default")
      (node (ref "IC26") (pin "3") (pinfunction "+IN_A_3") (pintype "input"))
      (node (ref "RN2") (pin "2") (pinfunction "2_2") (pintype "passive"))
      (node (ref "RN2") (pin "8") (pinfunction "8_8") (pintype "passive"))
    )
    (net (code "54") (name "Net-(IC26A--IN_A)") (class "Default")
      (node (ref "IC26") (pin "2") (pinfunction "-IN_A_2") (pintype "input"))
      (node (ref "RN2") (pin "3") (pinfunction "3_3") (pintype "passive"))
      (node (ref "RN2") (pin "5") (pinfunction "5_5") (pintype "passive"))
    )
    (net (code "55") (name "Net-(IC26B-+IN_B)") (class "Default")
      (node (ref "IC26") (pin "5") (pinfunction "+IN_B_5") (pintype "input"))
      (node (ref "RN3") (pin "3") (pinfunction "3_3") (pintype "passive"))
      (node (ref "RN3") (pin "7") (pinfunction "7_7") (pintype "passive"))
    )
    (net (code "56") (name "Net-(IC26B--IN_B)") (class "Default")
      (node (ref "IC26") (pin "6") (pinfunction "-IN_B_6") (pintype "input"))
      (node (ref "RN3") (pin "4") (pinfunction "4_4") (pintype "passive"))
      (node (ref "RN3") (pin "8") (pinfunction "8_8") (pintype "passive"))
    )
    (net (code "57") (name "Net-(IC27A--IN_A)") (class "Default")
      (node (ref "C126") (pin "2") (pinfunction "2_2") (pintype "passive"))
      (node (ref "IC27") (pin "2") (pinfunction "-IN_A_2") (pintype "input"))
      (node (ref "R156") (pin "2") (pinfunction "2_2") (pintype "passive"))
    )
    (net (code "58") (name "Net-(IC27A-OUT_A)") (class "Default")
      (node (ref "C126") (pin "1") (pinfunction "1_1") (pintype "passive"))
      (node (ref "IC27") (pin "1") (pinfunction "OUT_A_1") (pintype "output"))
      (node (ref "R158") (pin "1") (pinfunction "1_1") (pintype "passive"))
    )
    (net (code "59") (name "Net-(IC27B--IN_B)") (class "Default")
      (node (ref "C131") (pin "2") (pinfunction "2_2") (pintype "passive"))
      (node (ref "IC27") (pin "6") (pinfunction "-IN_B_6") (pintype "input"))
      (node (ref "R73") (pin "2") (pinfunction "2_2") (pintype "passive"))
    )
    (net (code "60") (name "Net-(IC27B-OUT_B)") (class "Default")
      (node (ref "C131") (pin "1") (pinfunction "1_1") (pintype "passive"))
      (node (ref "IC27") (pin "7") (pinfunction "OUT_B_7") (pintype "output"))
      (node (ref "R127") (pin "1") (pinfunction "1_1") (pintype "passive"))
    )
    (net (code "61") (name "Net-(J11-Pad1)") (class "Default")
      (node (ref "J11") (pin "1") (pinfunction "1_1") (pintype "bidirectional"))
      (node (ref "RN3") (pin "2") (pinfunction "2_2") (pintype "passive"))
    )
    (net (code "62") (name "Net-(J11-Pad2)") (class "Default")
      (node (ref "J11") (pin "2") (pinfunction "2_2") (pintype "bidirectional"))
      (node (ref "RN3") (pin "1") (pinfunction "1_1") (pintype "passive"))
    )
    (net (code "63") (name "P5V4A") (class "Default")
      (node (ref "C10") (pin "2") (pinfunction "2_2") (pintype "passive"))
      (node (ref "C107") (pin "2") (pinfunction "2_2") (pintype "passive"))
      (node (ref "C122") (pin "2") (pinfunction "2_2") (pintype "passive"))
      (node (ref "C127") (pin "2") (pinfunction "2_2") (pintype "passive"))
      (node (ref "C128") (pin "1") (pinfunction "1_1") (pintype "passive"))
      (node (ref "C13") (pin "1") (pinfunction "1_1") (pintype "passive"))
      (node (ref "C139") (pin "1") (pinfunction "1_1") (pintype "passive"))
      (node (ref "C149") (pin "2") (pinfunction "2_2") (pintype "passive"))
      (node (ref "C152") (pin "2") (pinfunction "2_2") (pintype "passive"))
      (node (ref "C4") (pin "2") (pinfunction "2_2") (pintype "passive"))
      (node (ref "C5") (pin "1") (pinfunction "1_1") (pintype "passive"))
      (node (ref "C8") (pin "2") (pinfunction "2_2") (pintype "passive"))
      (node (ref "IC1") (pin "1") (pinfunction "IN_1") (pintype "input"))
      (node (ref "IC1") (pin "2") (pinfunction "IN_2") (pintype "input"))
      (node (ref "IC1") (pin "6") (pinfunction "PGFB_6") (pintype "input"))
      (node (ref "IC11") (pin "2") (pinfunction "VIN_2") (pintype "input"))
      (node (ref "IC12") (pin "2") (pinfunction "VIN_2") (pintype "input"))
      (node (ref "IC14") (pin "1") (pinfunction "IN_1") (pintype "input"))
      (node (ref "IC14") (pin "2") (pinfunction "IN_2") (pintype "input"))
      (node (ref "IC14") (pin "6") (pinfunction "PGFB_6") (pintype "input"))
      (node (ref "IC19") (pin "1") (pinfunction "IN_1") (pintype "input"))
      (node (ref "IC19") (pin "2") (pinfunction "IN_2") (pintype "input"))
      (node (ref "IC19") (pin "6") (pinfunction "PGFB_6") (pintype "input"))
      (node (ref "IC2") (pin "8") (pinfunction "+V_8") (pintype "power_in"))
      (node (ref "IC20") (pin "1") (pinfunction "IN_1") (pintype "input"))
      (node (ref "IC20") (pin "2") (pinfunction "IN_2") (pintype "input"))
      (node (ref "IC20") (pin "6") (pinfunction "PGFB_6") (pintype "input"))
      (node (ref "IC26") (pin "8") (pinfunction "+V_8") (pintype "power_in"))
      (node (ref "IC27") (pin "8") (pinfunction "+V_8") (pintype "power_in"))
    )
    (net (code "64") (name "REF_P5V0") (class "Default")
      (node (ref "C140") (pin "2") (pinfunction "2_2") (pintype "passive"))
      (node (ref "IC19") (pin "10") (pinfunction "OUT_10") (pintype "output"))
      (node (ref "IC19") (pin "9") (pinfunction "OUTS_9") (pintype "output"))
      (node (ref "R1") (pin "1") (pinfunction "1_1") (pintype "passive"))
      (node (ref "R10") (pin "1") (pinfunction "1_1") (pintype "passive"))
      (node (ref "R12") (pin "1") (pinfunction "1_1") (pintype "passive"))
      (node (ref "R14") (pin "1") (pinfunction "1_1") (pintype "passive"))
      (node (ref "R154") (pin "2") (pinfunction "2_2") (pintype "passive"))
      (node (ref "R156") (pin "1") (pinfunction "1_1") (pintype "passive"))
      (node (ref "R272") (pin "1") (pinfunction "1_1") (pintype "passive"))
      (node (ref "R4") (pin "1") (pinfunction "1_1") (pintype "passive"))
      (node (ref "R5") (pin "1") (pinfunction "1_1") (pintype "passive"))
      (node (ref "R6") (pin "1") (pinfunction "1_1") (pintype "passive"))
      (node (ref "TP27") (pin "1") (pinfunction "1_1") (pintype "bidirectional"))
    )
    (net (code "65") (name "REF_P5V0b") (class "Default")
      (node (ref "C129") (pin "2") (pinfunction "2_2") (pintype "passive"))
      (node (ref "IC14") (pin "10") (pinfunction "OUT_10") (pintype "output"))
      (node (ref "IC14") (pin "9") (pinfunction "OUTS_9") (pintype "output"))
      (node (ref "R105") (pin "1") (pinfunction "1_1") (pintype "passive"))
      (node (ref "R106") (pin "1") (pinfunction "1_1") (pintype "passive"))
      (node (ref "R116") (pin "1") (pinfunction "1_1") (pintype "passive"))
      (node (ref "R118") (pin "1") (pinfunction "1_1") (pintype "passive"))
      (node (ref "R125") (pin "2") (pinfunction "2_2") (pintype "passive"))
      (node (ref "R16") (pin "1") (pinfunction "1_1") (pintype "passive"))
      (node (ref "R34") (pin "1") (pinfunction "1_1") (pintype "passive"))
      (node (ref "R58") (pin "1") (pinfunction "1_1") (pintype "passive"))
      (node (ref "R62") (pin "1") (pinfunction "1_1") (pintype "passive"))
      (node (ref "R73") (pin "1") (pinfunction "1_1") (pintype "passive"))
      (node (ref "TP28") (pin "1") (pinfunction "1_1") (pintype "bidirectional"))
    )
    (net (code "66") (name "REF_P5V0c") (class "Default")
      (node (ref "C6") (pin "2") (pinfunction "2_2") (pintype "passive"))
      (node (ref "IC1") (pin "10") (pinfunction "OUT_10") (pintype "output"))
      (node (ref "IC1") (pin "9") (pinfunction "OUTS_9") (pintype "output"))
      (node (ref "R124") (pin "1") (pinfunction "1_1") (pintype "passive"))
      (node (ref "R128") (pin "1") (pinfunction "1_1") (pintype "passive"))
      (node (ref "R129") (pin "1") (pinfunction "1_1") (pintype "passive"))
      (node (ref "R130") (pin "1") (pinfunction "1_1") (pintype "passive"))
      (node (ref "R131") (pin "1") (pinfunction "1_1") (pintype "passive"))
      (node (ref "R132") (pin "1") (pinfunction "1_1") (pintype "passive"))
      (node (ref "R133") (pin "1") (pinfunction "1_1") (pintype "passive"))
      (node (ref "R134") (pin "2") (pinfunction "2_2") (pintype "passive"))
      (node (ref "R136") (pin "1") (pinfunction "1_1") (pintype "passive"))
      (node (ref "R138") (pin "1") (pinfunction "1_1") (pintype "passive"))
      (node (ref "TP29") (pin "1") (pinfunction "1_1") (pintype "bidirectional"))
    )
    (net (code "67") (name "REF_P5V0d") (class "Default")
      (node (ref "C14") (pin "2") (pinfunction "2_2") (pintype "passive"))
      (node (ref "IC20") (pin "10") (pinfunction "OUT_10") (pintype "output"))
      (node (ref "IC20") (pin "9") (pinfunction "OUTS_9") (pintype "output"))
      (node (ref "R141") (pin "1") (pinfunction "1_1") (pintype "passive"))
      (node (ref "R144") (pin "1") (pinfunction "1_1") (pintype "passive"))
      (node (ref "R146") (pin "1") (pinfunction "1_1") (pintype "passive"))
      (node (ref "R147") (pin "1") (pinfunction "1_1") (pintype "passive"))
      (node (ref "R148") (pin "1") (pinfunction "1_1") (pintype "passive"))
      (node (ref "R149") (pin "1") (pinfunction "1_1") (pintype "passive"))
      (node (ref "R150") (pin "1") (pinfunction "1_1") (pintype "passive"))
      (node (ref "R161") (pin "2") (pinfunction "2_2") (pintype "passive"))
      (node (ref "R163") (pin "1") (pinfunction "1_1") (pintype "passive"))
      (node (ref "R166") (pin "1") (pinfunction "1_1") (pintype "passive"))
      (node (ref "TP30") (pin "1") (pinfunction "1_1") (pintype "bidirectional"))
    )
    (net (code "68") (name "Vaux1") (class "Default")
      (node (ref "RN2") (pin "4") (pinfunction "4_4") (pintype "passive"))
    )
    (net (code "69") (name "Vaux2") (class "Default")
      (node (ref "RN2") (pin "1") (pinfunction "1_1") (pintype "passive"))
    )
    (net (code "70") (name "unconnected-(IC1-PG-Pad4)") (class "Default")
      (node (ref "IC1") (pin "4") (pinfunction "PG_4") (pintype "output+no_connect"))
    )
    (net (code "71") (name "unconnected-(IC14-PG-Pad4)") (class "Default")
      (node (ref "IC14") (pin "4") (pinfunction "PG_4") (pintype "output+no_connect"))
    )
    (net (code "72") (name "unconnected-(IC19-PG-Pad4)") (class "Default")
      (node (ref "IC19") (pin "4") (pinfunction "PG_4") (pintype "output+no_connect"))
    )
    (net (code "73") (name "unconnected-(IC20-PG-Pad4)") (class "Default")
      (node (ref "IC20") (pin "4") (pinfunction "PG_4") (pintype "output+no_connect"))
    )
    (net (code "74") (name "unconnected-(SW2-Pad4)") (class "Default")
      (node (ref "SW2") (pin "4") (pinfunction "4_4") (pintype "bidirectional"))
    )
    (net (code "75") (name "unconnected-(SW2-Pad5)") (class "Default")
      (node (ref "SW2") (pin "5") (pinfunction "5_5") (pintype "bidirectional"))
    )
  )
)
